# daughter-pots2.net
KiCad netlist of a schematic drawn in EAGLE
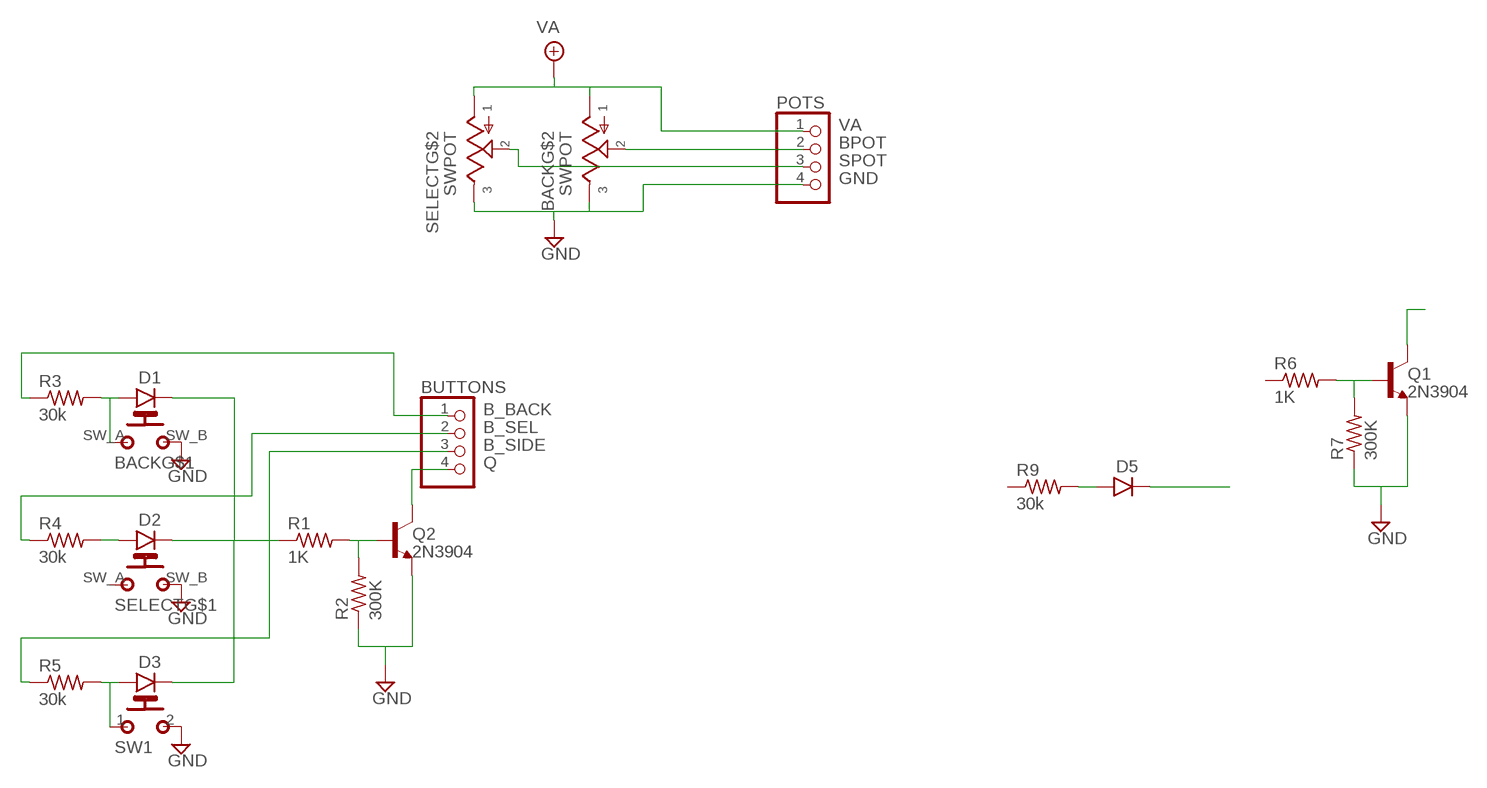
[diagram p0: schematic, sheet 1]

(export (version "E")
  (design (tool "Eeschema 10.0.6"))
  (components
    (comp (ref "BACK")
      (value "SWPOT")
      (footprint "eagle-import:SWPOT")
      (libsource (lib "eagle-import") (part "SWPOT"))
    )
    (comp (ref "BUTTONS")
      (value "PINHD-1X4")
      (footprint "eagle-import:1X04")
      (libsource (lib "eagle-import") (part "PINHD-1X4"))
    )
    (comp (ref "D1")
      (value "1N4148-3")
      (footprint "eagle-import:DO35-3")
      (libsource (lib "eagle-import") (part "1N4148-3"))
    )
    (comp (ref "D2")
      (value "1N4148-3")
      (footprint "eagle-import:DO35-3")
      (libsource (lib "eagle-import") (part "1N4148-3"))
    )
    (comp (ref "D3")
      (value "1N4148-3")
      (footprint "eagle-import:DO35-3")
      (libsource (lib "eagle-import") (part "1N4148-3"))
    )
    (comp (ref "D5")
      (value "1N4148-3")
      (footprint "eagle-import:DO35-3")
      (libsource (lib "eagle-import") (part "1N4148-3"))
    )
    (comp (ref "POTS")
      (value "PINHD-1X4")
      (footprint "eagle-import:1X04")
      (libsource (lib "eagle-import") (part "PINHD-1X4"))
    )
    (comp (ref "Q1")
      (value "2N3904")
      (footprint "eagle-import:TO92-")
      (libsource (lib "eagle-import") (part "2N3904"))
    )
    (comp (ref "Q2")
      (value "2N3904")
      (footprint "eagle-import:TO92-")
      (libsource (lib "eagle-import") (part "2N3904"))
    )
    (comp (ref "R1")
      (value "1K")
      (footprint "eagle-import:R0207_3")
      (libsource (lib "eagle-import") (part "6MM.3"))
    )
    (comp (ref "R2")
      (value "300K")
      (footprint "eagle-import:R0207_3")
      (libsource (lib "eagle-import") (part "6MM.3"))
    )
    (comp (ref "R3")
      (value "30k")
      (footprint "eagle-import:R0207_3")
      (libsource (lib "eagle-import") (part "6MM.3"))
    )
    (comp (ref "R4")
      (value "30k")
      (footprint "eagle-import:R0207_3")
      (libsource (lib "eagle-import") (part "6MM.3"))
    )
    (comp (ref "R5")
      (value "30k")
      (footprint "eagle-import:R0207_3")
      (libsource (lib "eagle-import") (part "6MM.3"))
    )
    (comp (ref "R6")
      (value "1K")
      (footprint "eagle-import:R0207_3")
      (libsource (lib "eagle-import") (part "6MM.3"))
    )
    (comp (ref "R7")
      (value "300K")
      (footprint "eagle-import:R0207_3")
      (libsource (lib "eagle-import") (part "6MM.3"))
    )
    (comp (ref "R9")
      (value "30k")
      (footprint "eagle-import:R0207_3")
      (libsource (lib "eagle-import") (part "6MM.3"))
    )
    (comp (ref "SELECT")
      (value "SWPOT")
      (footprint "eagle-import:SWPOT")
      (libsource (lib "eagle-import") (part "SWPOT"))
    )
    (comp (ref "SW1")
      (value "MOMENTARYSPST1")
      (footprint "eagle-import:SPST")
      (libsource (lib "eagle-import") (part "MOMENTARYSPST1"))
    )
  )
  (nets
    (net (code "1") (name "/BPOT") (class "Default")
      (node (ref "BACK") (pin "POT_W") (pinfunction "POT_W_POT_W") (pintype "passive"))
      (node (ref "POTS") (pin "2") (pinfunction "2_2") (pintype "passive"))
    )
    (net (code "2") (name "/B_BACK") (class "Default")
      (node (ref "BUTTONS") (pin "1") (pinfunction "1_1") (pintype "passive"))
      (node (ref "R3") (pin "1") (pinfunction "1_1") (pintype "passive"))
    )
    (net (code "3") (name "/B_SEL") (class "Default")
      (node (ref "BUTTONS") (pin "2") (pinfunction "2_2") (pintype "passive"))
      (node (ref "R4") (pin "1") (pinfunction "1_1") (pintype "passive"))
    )
    (net (code "4") (name "/B_SIDE") (class "Default")
      (node (ref "BUTTONS") (pin "3") (pinfunction "3_3") (pintype "passive"))
      (node (ref "R5") (pin "1") (pinfunction "1_1") (pintype "passive"))
    )
    (net (code "5") (name "/Q") (class "Default")
      (node (ref "BUTTONS") (pin "4") (pinfunction "4_4") (pintype "passive"))
      (node (ref "Q2") (pin "1") (pinfunction "C_1") (pintype "passive"))
    )
    (net (code "6") (name "/SPOT") (class "Default")
      (node (ref "POTS") (pin "3") (pinfunction "3_3") (pintype "passive"))
      (node (ref "SELECT") (pin "POT_W") (pinfunction "POT_W_POT_W") (pintype "passive"))
    )
    (net (code "7") (name "GND") (class "Default")
      (node (ref "BACK") (pin "POT_A") (pinfunction "POT_A_POT_A") (pintype "passive"))
      (node (ref "BACK") (pin "SW_B") (pinfunction "B_B_SW_B") (pintype "passive"))
      (node (ref "POTS") (pin "4") (pinfunction "4_4") (pintype "passive"))
      (node (ref "Q1") (pin "3") (pinfunction "E_3") (pintype "passive"))
      (node (ref "Q2") (pin "3") (pinfunction "E_3") (pintype "passive"))
      (node (ref "R2") (pin "1") (pinfunction "1_1") (pintype "passive"))
      (node (ref "R7") (pin "1") (pinfunction "1_1") (pintype "passive"))
      (node (ref "SELECT") (pin "POT_A") (pinfunction "POT_A_POT_A") (pintype "passive"))
      (node (ref "SELECT") (pin "SW_B") (pinfunction "B_B_SW_B") (pintype "passive"))
      (node (ref "SW1") (pin "2") (pinfunction "S_2") (pintype "passive"))
    )
    (net (code "8") (name "Net-(BACKA-B_A)") (class "Default")
      (node (ref "BACK") (pin "SW_A") (pinfunction "B_A_SW_A") (pintype "passive"))
      (node (ref "D1") (pin "A") (pinfunction "A_A") (pintype "passive"))
      (node (ref "R3") (pin "2") (pinfunction "2_2") (pintype "passive"))
    )
    (net (code "9") (name "Net-(D1-PadC)") (class "Default")
      (node (ref "D1") (pin "C") (pinfunction "C_C") (pintype "passive"))
      (node (ref "D2") (pin "C") (pinfunction "C_C") (pintype "passive"))
      (node (ref "D3") (pin "C") (pinfunction "C_C") (pintype "passive"))
      (node (ref "R1") (pin "1") (pinfunction "1_1") (pintype "passive"))
    )
    (net (code "10") (name "Net-(D2-PadA)") (class "Default")
      (node (ref "D2") (pin "A") (pinfunction "A_A") (pintype "passive"))
      (node (ref "R4") (pin "2") (pinfunction "2_2") (pintype "passive"))
    )
    (net (code "11") (name "Net-(D5-PadA)") (class "Default")
      (node (ref "D5") (pin "A") (pinfunction "A_A") (pintype "passive"))
      (node (ref "R9") (pin "2") (pinfunction "2_2") (pintype "passive"))
    )
    (net (code "12") (name "Net-(Q1-B)") (class "Default")
      (node (ref "Q1") (pin "2") (pinfunction "B_2") (pintype "passive"))
      (node (ref "R6") (pin "2") (pinfunction "2_2") (pintype "passive"))
      (node (ref "R7") (pin "2") (pinfunction "2_2") (pintype "passive"))
    )
    (net (code "13") (name "Net-(Q2-B)") (class "Default")
      (node (ref "Q2") (pin "2") (pinfunction "B_2") (pintype "passive"))
      (node (ref "R1") (pin "2") (pinfunction "2_2") (pintype "passive"))
      (node (ref "R2") (pin "2") (pinfunction "2_2") (pintype "passive"))
    )
    (net (code "14") (name "Net-(SW1-P)") (class "Default")
      (node (ref "D3") (pin "A") (pinfunction "A_A") (pintype "passive"))
      (node (ref "R5") (pin "2") (pinfunction "2_2") (pintype "passive"))
      (node (ref "SW1") (pin "1") (pinfunction "P_1") (pintype "passive"))
    )
    (net (code "15") (name "VA") (class "Default")
      (node (ref "BACK") (pin "POT_B") (pinfunction "POT_B_POT_B") (pintype "passive"))
      (node (ref "POTS") (pin "1") (pinfunction "1_1") (pintype "passive"))
      (node (ref "SELECT") (pin "POT_B") (pinfunction "POT_B_POT_B") (pintype "passive"))
    )
    (net (code "16") (name "unconnected-(D5-PadC)") (class "Default")
      (node (ref "D5") (pin "C") (pinfunction "C_C") (pintype "passive"))
    )
    (net (code "17") (name "unconnected-(Q1-C-Pad1)") (class "Default")
      (node (ref "Q1") (pin "1") (pinfunction "C_1") (pintype "passive"))
    )
    (net (code "18") (name "unconnected-(R6-Pad1)") (class "Default")
      (node (ref "R6") (pin "1") (pinfunction "1_1") (pintype "passive"))
    )
    (net (code "19") (name "unconnected-(R9-Pad1)") (class "Default")
      (node (ref "R9") (pin "1") (pinfunction "1_1") (pintype "passive"))
    )
    (net (code "20") (name "unconnected-(SELECTA-B_A-PadSW_A)") (class "Default")
      (node (ref "SELECT") (pin "SW_A") (pinfunction "B_A_SW_A") (pintype "passive"))
    )
  )
)
